# FMU_Power_FMU_REV_1B.net
KiCad netlist of a schematic drawn in Altium Designer
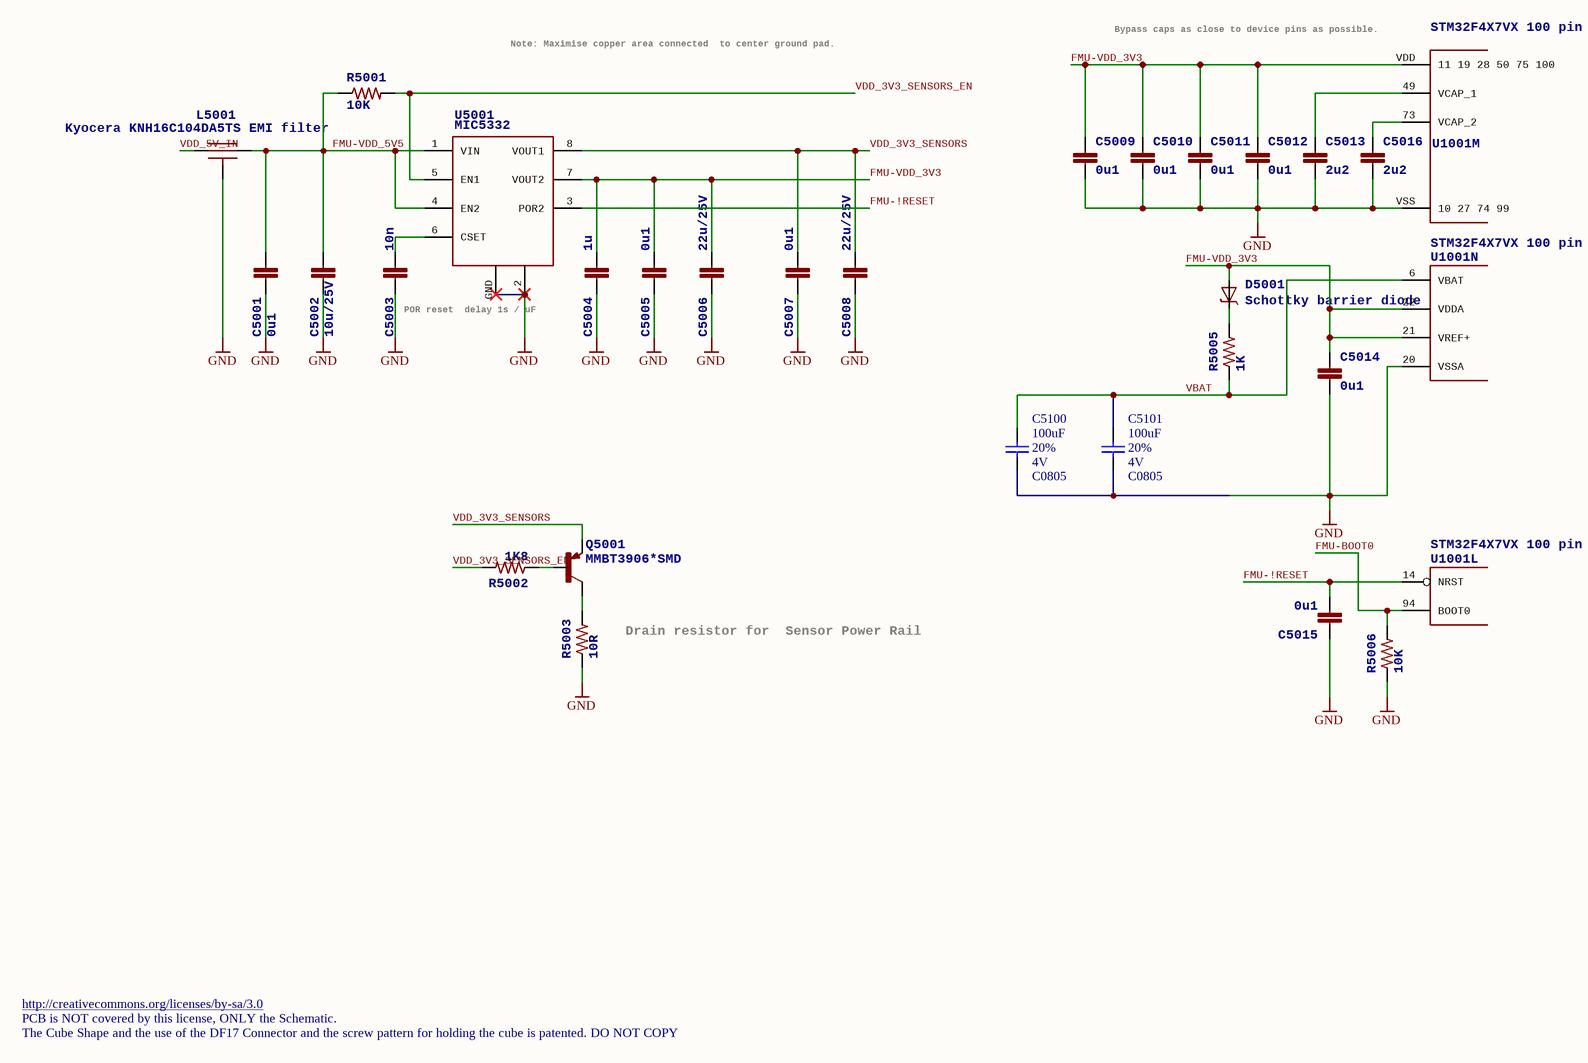
[diagram p0: FMU_Power_FMU_REV_1B.SchDoc]

(export (version "E")
  (design (tool "Eeschema 10.0.6"))
  (components
    (comp (ref "C5001")
      (value "0u1")
      (footprint "0402-CAP")
      (description "CAP CER 0.1UF 16V Y5V 0402")
      (libsource (lib "pixhawk2") (part "CAP0402"))
    )
    (comp (ref "C5002")
      (value "10u/25V")
      (footprint "0805-CAP")
      (description "CAP CER 10UF 25V 10% X5R 0805")
      (libsource (lib "pixhawk2") (part "CAP0805"))
    )
    (comp (ref "C5003")
      (value "10n")
      (footprint "0402-CAP")
      (description "CAP CER 10000PF 16V 10% X7R 0402")
      (libsource (lib "") (part "CAP0402_1"))
    )
    (comp (ref "C5004")
      (value "1u")
      (footprint "0603-CAP")
      (description "CAP CER 1UF 16V Y5V 0603")
      (libsource (lib "pixhawk2") (part "CAP0603"))
    )
    (comp (ref "C5005")
      (value "0u1")
      (footprint "0402-CAP")
      (description "CAP CER 0.1UF 16V Y5V 0402")
      (libsource (lib "pixhawk2") (part "CAP0402"))
    )
    (comp (ref "C5006")
      (value "22u/25V")
      (footprint "0805-CAP")
      (description "CAP CER 22UF 25V 20% X5R 0805")
      (libsource (lib "pixhawk2") (part "CAP0805"))
    )
    (comp (ref "C5007")
      (value "0u1")
      (footprint "0402-CAP")
      (description "CAP CER 0.1UF 16V Y5V 0402")
      (libsource (lib "pixhawk2") (part "CAP0402"))
    )
    (comp (ref "C5008")
      (value "22u/25V")
      (footprint "0805-CAP")
      (description "CAP CER 22UF 25V 20% X5R 0805")
      (libsource (lib "pixhawk2") (part "CAP0805"))
    )
    (comp (ref "C5009")
      (value "0u1")
      (footprint "0402-CAP")
      (description "CAP CER 0.1UF 16V Y5V 0402")
      (libsource (lib "pixhawk2") (part "CAP0402"))
    )
    (comp (ref "C5010")
      (value "0u1")
      (footprint "0402-CAP")
      (description "CAP CER 0.1UF 16V Y5V 0402")
      (libsource (lib "pixhawk2") (part "CAP0402"))
    )
    (comp (ref "C5011")
      (value "0u1")
      (footprint "0402-CAP")
      (description "CAP CER 0.1UF 16V Y5V 0402")
      (libsource (lib "pixhawk2") (part "CAP0402"))
    )
    (comp (ref "C5012")
      (value "0u1")
      (footprint "0402-CAP")
      (description "CAP CER 0.1UF 16V Y5V 0402")
      (libsource (lib "pixhawk2") (part "CAP0402"))
    )
    (comp (ref "C5013")
      (value "2u2")
      (footprint "0603-CAP")
      (description "CAP CER 2.2UF 16V 10% X6S 0603")
      (libsource (lib "pixhawk2") (part "CAP0603"))
    )
    (comp (ref "C5014")
      (value "0u1")
      (footprint "0402-CAP")
      (description "CAP CER 0.1UF 16V Y5V 0402")
      (libsource (lib "pixhawk2") (part "CAP0402"))
    )
    (comp (ref "C5015")
      (value "0u1")
      (footprint "0402-CAP")
      (description "CAP CER 0.1UF 16V Y5V 0402")
      (libsource (lib "") (part "CAP0402_2"))
    )
    (comp (ref "C5016")
      (value "2u2")
      (footprint "0603-CAP")
      (description "CAP CER 2.2UF 16V 10% X6S 0603")
      (libsource (lib "pixhawk2") (part "CAP0603"))
    )
    (comp (ref "C5100")
      (value "100uF")
      (footprint "C0805")
      (fields
        (field (name "TOLERANCE") "20%")
        (field (name "VOLTAGE") "4V")
        (field (name "Comment") "GRM21BR60G107ME15L")
      )
      (libsource (lib "3DR") (part "Capacitor"))
    )
    (comp (ref "C5101")
      (value "100uF")
      (footprint "C0805")
      (fields
        (field (name "TOLERANCE") "20%")
        (field (name "VOLTAGE") "4V")
        (field (name "Comment") "GRM21BR60G107ME15L")
      )
      (libsource (lib "3DR") (part "Capacitor"))
    )
    (comp (ref "D5001")
      (value "Schottky barrier diode")
      (footprint "SOD323")
      (description "DIODE SCHOTTKY 30V 0.03A SOD323")
      (libsource (lib "pixhawk2") (part "DIODE-SCHOTTKY_SOD323"))
    )
    (comp (ref "L5001")
      (value "Kyocera KNH16C104DA5TS EMI filter")
      (footprint "KYOCERA-KNH16-DA")
      (description "FILTER CAP 0.1UF 2A 25V 0603")
      (libsource (lib "pixhawk2") (part "KNH16C104DA5TS"))
    )
    (comp (ref "Q5001")
      (value "MMBT3906*SMD")
      (footprint "SOT23-BEC")
      (description "TRANSISTOR SWITCHING PNP SOT-23")
      (libsource (lib "transistor-pnp") (part "MMBT3906*SMD"))
    )
    (comp (ref "R5001")
      (value "10K")
      (footprint "0402-RES")
      (description "RES 10K OHM 1/16W 1% 0402 SMD")
      (libsource (lib "pixhawk2") (part "RESISTOR0402-RES"))
    )
    (comp (ref "R5002")
      (value "1K8")
      (footprint "0402-RES")
      (description "RES 1.8K OHM 1/16W 1% 0402")
      (libsource (lib "pixhawk2") (part "RESISTOR0402-RES"))
    )
    (comp (ref "R5003")
      (value "10R")
      (footprint "0603-RES")
      (description "RES 10 OHM 1/10W 5% 0603")
      (libsource (lib "pixhawk2") (part "RESISTOR0603-RES"))
    )
    (comp (ref "R5005")
      (value "1K")
      (footprint "0402-RES")
      (description "RES 1K OHM 1/16W 1% 0402")
      (libsource (lib "pixhawk2") (part "RESISTOR0402-RES"))
    )
    (comp (ref "R5006")
      (value "10K")
      (footprint "0402-RES")
      (description "RES 10K OHM 1/16W 1% 0402 SMD")
      (libsource (lib "pixhawk2") (part "RESISTOR0402-RES"))
    )
    (comp (ref "U1001")
      (value "STM32F4X7VX 100 pin")
      (footprint "TQFP100")
      (description "REV 3 Silicon or later IC MCU ARM 2MB FLASH 100LQFP")
      (libsource (lib "pixhawk2") (part "STM32F4X7VX"))
    )
    (comp (ref "U5001")
      (value "MIC5332")
      (footprint "MLF-8-EPAD")
      (description "IC REG LDO 3.3V 0.3A 8TMLF")
      (libsource (lib "pixhawk2") (part "MIC5332"))
    )
  )
  (nets
    (net (code "1") (name "/FMU-!RESET") (class "Default")
      (node (ref "C5015") (pin "P$2") (pinfunction "2_P$2") (pintype "passive"))
      (node (ref "U1001") (pin "14") (pinfunction "NRST_14") (pintype "passive"))
      (node (ref "U5001") (pin "3") (pinfunction "POR2_3") (pintype "passive"))
    )
    (net (code "2") (name "/FMU-BOOT0") (class "Default")
      (node (ref "R5006") (pin "P$2") (pinfunction "2_P$2") (pintype "passive"))
      (node (ref "U1001") (pin "94") (pinfunction "BOOT0_94") (pintype "passive"))
    )
    (net (code "3") (name "/FMU-VDD_3V3") (class "Default")
      (node (ref "C5004") (pin "P$1") (pinfunction "1_P$1") (pintype "passive"))
      (node (ref "C5005") (pin "P$1") (pinfunction "1_P$1") (pintype "passive"))
      (node (ref "C5006") (pin "P$1") (pinfunction "1_P$1") (pintype "passive"))
      (node (ref "C5009") (pin "P$1") (pinfunction "1_P$1") (pintype "passive"))
      (node (ref "C5010") (pin "P$1") (pinfunction "1_P$1") (pintype "passive"))
      (node (ref "C5011") (pin "P$1") (pinfunction "1_P$1") (pintype "passive"))
      (node (ref "C5012") (pin "P$1") (pinfunction "1_P$1") (pintype "passive"))
      (node (ref "C5014") (pin "P$1") (pinfunction "1_P$1") (pintype "passive"))
      (node (ref "D5001") (pin "A") (pinfunction "A_A") (pintype "passive"))
      (node (ref "U1001") (pin "21") (pinfunction "VREF+_21") (pintype "passive"))
      (node (ref "U1001") (pin "22") (pinfunction "VDDA_22") (pintype "power_in"))
      (node (ref "U1001") (pin "VDD") (pinfunction "11_19_28_50_75_100_VDD") (pintype "power_in"))
      (node (ref "U5001") (pin "7") (pinfunction "VOUT2_7") (pintype "passive"))
    )
    (net (code "4") (name "/FMU-VDD_5V5") (class "Default")
      (node (ref "C5001") (pin "P$1") (pinfunction "1_P$1") (pintype "passive"))
      (node (ref "C5002") (pin "P$1") (pinfunction "1_P$1") (pintype "passive"))
      (node (ref "L5001") (pin "P$2") (pinfunction "P$2_P$2") (pintype "passive"))
      (node (ref "R5001") (pin "P$1") (pinfunction "1_P$1") (pintype "passive"))
      (node (ref "U5001") (pin "1") (pinfunction "VIN_1") (pintype "passive"))
      (node (ref "U5001") (pin "4") (pinfunction "EN2_4") (pintype "passive"))
    )
    (net (code "5") (name "/VBAT") (class "Default")
      (node (ref "C5100") (pin "2") (pinfunction "2_2") (pintype "passive"))
      (node (ref "C5101") (pin "2") (pinfunction "2_2") (pintype "passive"))
      (node (ref "R5005") (pin "P$1") (pinfunction "1_P$1") (pintype "passive"))
      (node (ref "U1001") (pin "6") (pinfunction "VBAT_6") (pintype "power_in"))
    )
    (net (code "6") (name "/VDD_3V3_SENSORS") (class "Default")
      (node (ref "C5007") (pin "P$1") (pinfunction "1_P$1") (pintype "passive"))
      (node (ref "C5008") (pin "P$1") (pinfunction "1_P$1") (pintype "passive"))
      (node (ref "Q5001") (pin "E") (pinfunction "E_E") (pintype "passive"))
      (node (ref "U5001") (pin "8") (pinfunction "VOUT1_8") (pintype "passive"))
    )
    (net (code "7") (name "/VDD_3V3_SENSORS_EN") (class "Default")
      (node (ref "R5001") (pin "P$2") (pinfunction "2_P$2") (pintype "passive"))
      (node (ref "R5002") (pin "P$2") (pinfunction "2_P$2") (pintype "passive"))
      (node (ref "U5001") (pin "5") (pinfunction "EN1_5") (pintype "passive"))
    )
    (net (code "8") (name "/VDD_5V_IN") (class "Default")
      (node (ref "L5001") (pin "P$1") (pinfunction "P$1_P$1") (pintype "passive"))
    )
    (net (code "9") (name "GND") (class "Default")
      (node (ref "C5001") (pin "P$2") (pinfunction "2_P$2") (pintype "passive"))
      (node (ref "C5002") (pin "P$2") (pinfunction "2_P$2") (pintype "passive"))
      (node (ref "C5003") (pin "P$1") (pinfunction "1_P$1") (pintype "passive"))
      (node (ref "C5004") (pin "P$2") (pinfunction "2_P$2") (pintype "passive"))
      (node (ref "C5005") (pin "P$2") (pinfunction "2_P$2") (pintype "passive"))
      (node (ref "C5006") (pin "P$2") (pinfunction "2_P$2") (pintype "passive"))
      (node (ref "C5007") (pin "P$2") (pinfunction "2_P$2") (pintype "passive"))
      (node (ref "C5008") (pin "P$2") (pinfunction "2_P$2") (pintype "passive"))
      (node (ref "C5009") (pin "P$2") (pinfunction "2_P$2") (pintype "passive"))
      (node (ref "C5010") (pin "P$2") (pinfunction "2_P$2") (pintype "passive"))
      (node (ref "C5011") (pin "P$2") (pinfunction "2_P$2") (pintype "passive"))
      (node (ref "C5012") (pin "P$2") (pinfunction "2_P$2") (pintype "passive"))
      (node (ref "C5013") (pin "P$2") (pinfunction "2_P$2") (pintype "passive"))
      (node (ref "C5014") (pin "P$2") (pinfunction "2_P$2") (pintype "passive"))
      (node (ref "C5015") (pin "P$1") (pinfunction "1_P$1") (pintype "passive"))
      (node (ref "C5016") (pin "P$2") (pinfunction "2_P$2") (pintype "passive"))
      (node (ref "C5100") (pin "1") (pinfunction "1_1") (pintype "passive"))
      (node (ref "C5101") (pin "1") (pinfunction "1_1") (pintype "passive"))
      (node (ref "L5001") (pin "GND") (pinfunction "GND_GND") (pintype "passive"))
      (node (ref "R5003") (pin "1") (pinfunction "1_1") (pintype "passive"))
      (node (ref "R5006") (pin "P$1") (pinfunction "1_P$1") (pintype "passive"))
      (node (ref "U1001") (pin "20") (pinfunction "VSSA_20") (pintype "power_in"))
      (node (ref "U1001") (pin "VSS") (pinfunction "10_27_74_99_VSS") (pintype "power_in"))
      (node (ref "U5001") (pin "2") (pinfunction "GND_2") (pintype "power_in"))
      (node (ref "U5001") (pin "GND") (pinfunction "GND_GND") (pintype "power_in"))
    )
    (net (code "10") (name "Net-(C5003-2)") (class "Default")
      (node (ref "C5003") (pin "P$2") (pinfunction "2_P$2") (pintype "passive"))
      (node (ref "U5001") (pin "6") (pinfunction "CSET_6") (pintype "passive"))
    )
    (net (code "11") (name "Net-(C5013-1)") (class "Default")
      (node (ref "C5013") (pin "P$1") (pinfunction "1_P$1") (pintype "passive"))
      (node (ref "U1001") (pin "49") (pinfunction "VCAP_1_49") (pintype "power_in"))
    )
    (net (code "12") (name "Net-(C5016-1)") (class "Default")
      (node (ref "C5016") (pin "P$1") (pinfunction "1_P$1") (pintype "passive"))
      (node (ref "U1001") (pin "73") (pinfunction "VCAP_2_73") (pintype "power_in"))
    )
    (net (code "13") (name "Net-(Q5001-PadC)") (class "Default")
      (node (ref "Q5001") (pin "C") (pinfunction "C_C") (pintype "passive"))
      (node (ref "R5003") (pin "2") (pinfunction "2_2") (pintype "passive"))
    )
    (net (code "14") (name "Net-(R5002-1)") (class "Default")
      (node (ref "Q5001") (pin "B") (pinfunction "B_B") (pintype "passive"))
      (node (ref "R5002") (pin "P$1") (pinfunction "1_P$1") (pintype "passive"))
    )
    (net (code "15") (name "Net-(R5005-2)") (class "Default")
      (node (ref "D5001") (pin "C") (pinfunction "C_C") (pintype "passive"))
      (node (ref "R5005") (pin "P$2") (pinfunction "2_P$2") (pintype "passive"))
    )
  )
)
